# V1.net
KiCad netlist of a schematic drawn in EAGLE
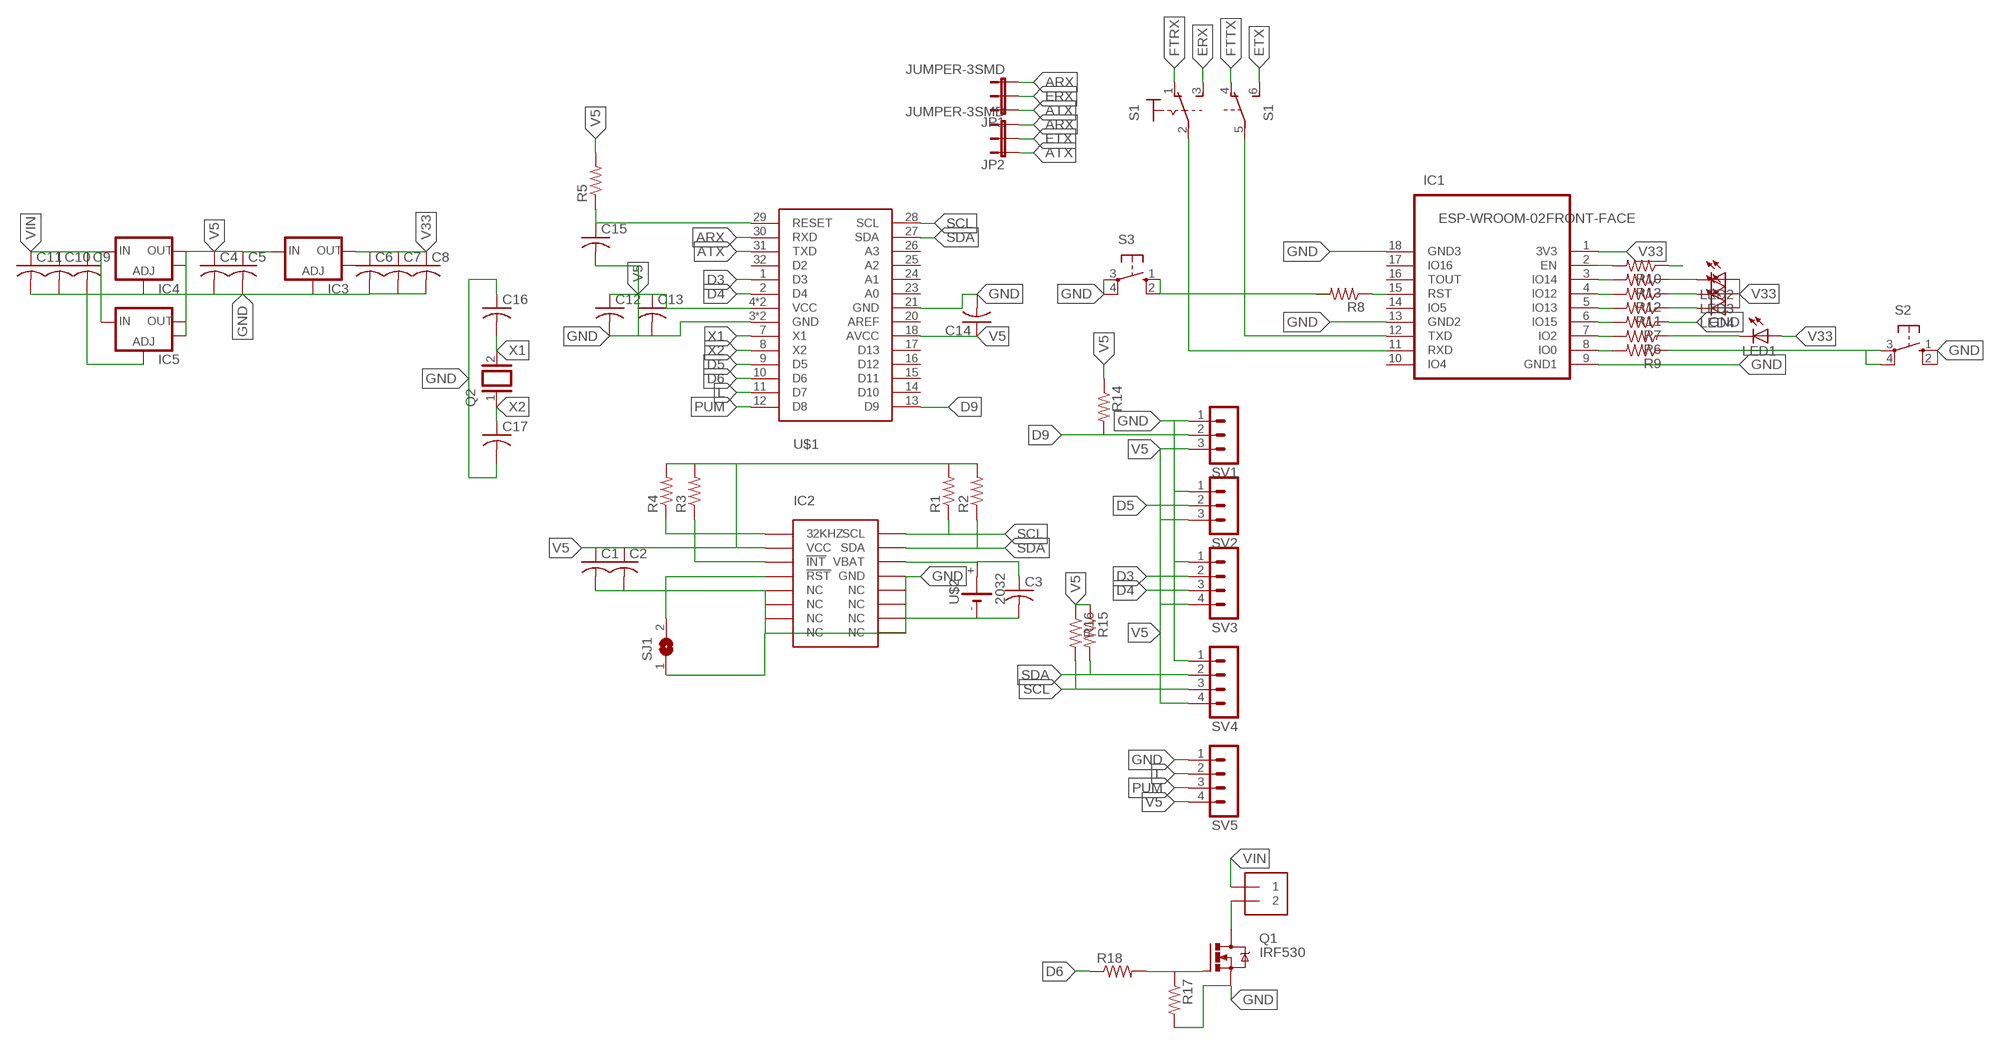
[diagram p0: schematic, sheet 1]

(export (version "E")
  (design (tool "Eeschema 10.0.6"))
  (components
    (comp (ref "C1")
      (value "C-USC0805")
      (footprint "eagle-import:C0805")
      (libsource (lib "eagle-import") (part "C-USC0805"))
    )
    (comp (ref "C2")
      (value "C-USC0805")
      (footprint "eagle-import:C0805")
      (libsource (lib "eagle-import") (part "C-USC0805"))
    )
    (comp (ref "C3")
      (value "C-USC0805")
      (footprint "eagle-import:C0805")
      (libsource (lib "eagle-import") (part "C-USC0805"))
    )
    (comp (ref "C4")
      (value "C-USC0805")
      (footprint "eagle-import:C0805")
      (libsource (lib "eagle-import") (part "C-USC0805"))
    )
    (comp (ref "C5")
      (value "C-USC0805")
      (footprint "eagle-import:C0805")
      (libsource (lib "eagle-import") (part "C-USC0805"))
    )
    (comp (ref "C6")
      (value "C-USC0805")
      (footprint "eagle-import:C0805")
      (libsource (lib "eagle-import") (part "C-USC0805"))
    )
    (comp (ref "C7")
      (value "C-USC0805")
      (footprint "eagle-import:C0805")
      (libsource (lib "eagle-import") (part "C-USC0805"))
    )
    (comp (ref "C8")
      (value "C-USC0805")
      (footprint "eagle-import:C0805")
      (libsource (lib "eagle-import") (part "C-USC0805"))
    )
    (comp (ref "C9")
      (value "C-USC0805")
      (footprint "eagle-import:C0805")
      (libsource (lib "eagle-import") (part "C-USC0805"))
    )
    (comp (ref "C10")
      (value "C-USC0805")
      (footprint "eagle-import:C0805")
      (libsource (lib "eagle-import") (part "C-USC0805"))
    )
    (comp (ref "C11")
      (value "C-USC0805")
      (footprint "eagle-import:C0805")
      (libsource (lib "eagle-import") (part "C-USC0805"))
    )
    (comp (ref "C12")
      (value "C-USC0805")
      (footprint "eagle-import:C0805")
      (libsource (lib "eagle-import") (part "C-USC0805"))
    )
    (comp (ref "C13")
      (value "C-USC0805")
      (footprint "eagle-import:C0805")
      (libsource (lib "eagle-import") (part "C-USC0805"))
    )
    (comp (ref "C14")
      (value "C-USC0805")
      (footprint "eagle-import:C0805")
      (libsource (lib "eagle-import") (part "C-USC0805"))
    )
    (comp (ref "C15")
      (value "C-USC0805")
      (footprint "eagle-import:C0805")
      (libsource (lib "eagle-import") (part "C-USC0805"))
    )
    (comp (ref "C16")
      (value "C-USC0805")
      (footprint "eagle-import:C0805")
      (libsource (lib "eagle-import") (part "C-USC0805"))
    )
    (comp (ref "C17")
      (value "C-USC0805")
      (footprint "eagle-import:C0805")
      (libsource (lib "eagle-import") (part "C-USC0805"))
    )
    (comp (ref "IC1")
      (value "ESP-WROOM-02FRONT-FACE")
      (footprint "eagle-import:FRONT-FACE")
      (libsource (lib "eagle-import") (part "ESP-WROOM-02FRONT-FACE"))
    )
    (comp (ref "IC2")
      (value "DS3231SOIC-16W")
      (footprint "eagle-import:SOIC-16W")
      (libsource (lib "eagle-import") (part "DS3231SOIC-16W"))
    )
    (comp (ref "IC3")
      (value "V_REG_LM1117SOT223")
      (footprint "eagle-import:SOT223")
      (libsource (lib "eagle-import") (part "V_REG_LM1117SOT223"))
    )
    (comp (ref "IC4")
      (value "V_REG_LM1117SOT223")
      (footprint "eagle-import:SOT223")
      (libsource (lib "eagle-import") (part "V_REG_LM1117SOT223"))
    )
    (comp (ref "IC5")
      (value "V_REG_LM1117SOT223")
      (footprint "eagle-import:SOT223")
      (libsource (lib "eagle-import") (part "V_REG_LM1117SOT223"))
    )
    (comp (ref "J1")
      (value "1X2-3.5MM")
      (footprint "eagle-import:3.5MMTERM")
      (libsource (lib "eagle-import") (part "1X2-3.5MM"))
    )
    (comp (ref "JP1")
      (value "JUMPER-3SMD")
      (footprint "eagle-import:SJ_3")
      (libsource (lib "eagle-import") (part "JUMPER-3SMD"))
    )
    (comp (ref "JP2")
      (value "JUMPER-3SMD")
      (footprint "eagle-import:SJ_3")
      (libsource (lib "eagle-import") (part "JUMPER-3SMD"))
    )
    (comp (ref "LED1")
      (value "LED5MM")
      (footprint "eagle-import:LED5MM")
      (libsource (lib "eagle-import") (part "LED5MM"))
    )
    (comp (ref "LED2")
      (value "LED5MM")
      (footprint "eagle-import:LED5MM")
      (libsource (lib "eagle-import") (part "LED5MM"))
    )
    (comp (ref "LED3")
      (value "LED5MM")
      (footprint "eagle-import:LED5MM")
      (libsource (lib "eagle-import") (part "LED5MM"))
    )
    (comp (ref "LED4")
      (value "LED5MM")
      (footprint "eagle-import:LED5MM")
      (libsource (lib "eagle-import") (part "LED5MM"))
    )
    (comp (ref "Q1")
      (value "IRF530")
      (footprint "eagle-import:TO220BV")
      (libsource (lib "eagle-import") (part "IRF530"))
    )
    (comp (ref "Q2")
      (value "XTAL/S")
      (footprint "eagle-import:QS")
      (libsource (lib "eagle-import") (part "XTAL/S"))
    )
    (comp (ref "R1")
      (value "R-US_R0805")
      (footprint "eagle-import:R0805")
      (libsource (lib "eagle-import") (part "R-US_R0805"))
    )
    (comp (ref "R2")
      (value "R-US_R0805")
      (footprint "eagle-import:R0805")
      (libsource (lib "eagle-import") (part "R-US_R0805"))
    )
    (comp (ref "R3")
      (value "R-US_R0805")
      (footprint "eagle-import:R0805")
      (libsource (lib "eagle-import") (part "R-US_R0805"))
    )
    (comp (ref "R4")
      (value "R-US_R0805")
      (footprint "eagle-import:R0805")
      (libsource (lib "eagle-import") (part "R-US_R0805"))
    )
    (comp (ref "R5")
      (value "R-US_R0805")
      (footprint "eagle-import:R0805")
      (libsource (lib "eagle-import") (part "R-US_R0805"))
    )
    (comp (ref "R6")
      (value "R-US_R0805")
      (footprint "eagle-import:R0805")
      (libsource (lib "eagle-import") (part "R-US_R0805"))
    )
    (comp (ref "R7")
      (value "R-US_R0805")
      (footprint "eagle-import:R0805")
      (libsource (lib "eagle-import") (part "R-US_R0805"))
    )
    (comp (ref "R8")
      (value "R-US_R0805")
      (footprint "eagle-import:R0805")
      (libsource (lib "eagle-import") (part "R-US_R0805"))
    )
    (comp (ref "R9")
      (value "R-US_R0805")
      (footprint "eagle-import:R0805")
      (libsource (lib "eagle-import") (part "R-US_R0805"))
    )
    (comp (ref "R10")
      (value "R-US_R0805")
      (footprint "eagle-import:R0805")
      (libsource (lib "eagle-import") (part "R-US_R0805"))
    )
    (comp (ref "R11")
      (value "R-US_R0805")
      (footprint "eagle-import:R0805")
      (libsource (lib "eagle-import") (part "R-US_R0805"))
    )
    (comp (ref "R12")
      (value "R-US_R0805")
      (footprint "eagle-import:R0805")
      (libsource (lib "eagle-import") (part "R-US_R0805"))
    )
    (comp (ref "R13")
      (value "R-US_R0805")
      (footprint "eagle-import:R0805")
      (libsource (lib "eagle-import") (part "R-US_R0805"))
    )
    (comp (ref "R14")
      (value "R-US_R0805")
      (footprint "eagle-import:R0805")
      (libsource (lib "eagle-import") (part "R-US_R0805"))
    )
    (comp (ref "R15")
      (value "R-US_R0805")
      (footprint "eagle-import:R0805")
      (libsource (lib "eagle-import") (part "R-US_R0805"))
    )
    (comp (ref "R16")
      (value "R-US_R0805")
      (footprint "eagle-import:R0805")
      (libsource (lib "eagle-import") (part "R-US_R0805"))
    )
    (comp (ref "R17")
      (value "R-US_R0805")
      (footprint "eagle-import:R0805")
      (libsource (lib "eagle-import") (part "R-US_R0805"))
    )
    (comp (ref "R18")
      (value "R-US_R0805")
      (footprint "eagle-import:R0805")
      (libsource (lib "eagle-import") (part "R-US_R0805"))
    )
    (comp (ref "S1")
      (value "320-938")
      (footprint "eagle-import:320-938")
      (libsource (lib "eagle-import") (part "320-938"))
    )
    (comp (ref "S2")
      (value "10-XX")
      (footprint "eagle-import:B3F-10XX")
      (fields (field (name "MPN") "B3F-1000"))
      (libsource (lib "eagle-import") (part "10-XX"))
    )
    (comp (ref "S3")
      (value "10-XX")
      (footprint "eagle-import:B3F-10XX")
      (fields (field (name "MPN") "B3F-1000"))
      (libsource (lib "eagle-import") (part "10-XX"))
    )
    (comp (ref "SJ1")
      (value "SJW")
      (footprint "eagle-import:SJW")
      (libsource (lib "eagle-import") (part "SJW"))
    )
    (comp (ref "SV1")
      (value "MA03-1")
      (footprint "eagle-import:MA03-1")
      (libsource (lib "eagle-import") (part "MA03-1"))
    )
    (comp (ref "SV2")
      (value "MA03-1")
      (footprint "eagle-import:MA03-1")
      (libsource (lib "eagle-import") (part "MA03-1"))
    )
    (comp (ref "SV3")
      (value "MA04-1")
      (footprint "eagle-import:MA04-1")
      (libsource (lib "eagle-import") (part "MA04-1"))
    )
    (comp (ref "SV4")
      (value "MA04-1")
      (footprint "eagle-import:MA04-1")
      (libsource (lib "eagle-import") (part "MA04-1"))
    )
    (comp (ref "SV5")
      (value "MA04-1")
      (footprint "eagle-import:MA04-1")
      (libsource (lib "eagle-import") (part "MA04-1"))
    )
    (comp (ref "U$1")
      (value "ATMEGA328P")
      (footprint "eagle-import:TQFP32-08")
      (libsource (lib "eagle-import") (part "ATMEGA328P"))
    )
    (comp (ref "U$2")
      (value "2032")
      (footprint "eagle-import:KZH20SMD")
      (libsource (lib "eagle-import") (part "2032"))
    )
  )
  (nets
    (net (code "1") (name "ARX") (class "Default")
      (node (ref "C15") (pin "1") (pinfunction "1_1") (pintype "passive"))
      (node (ref "JP1") (pin "3") (pinfunction "3_3") (pintype "passive"))
      (node (ref "JP2") (pin "3") (pinfunction "3_3") (pintype "passive"))
      (node (ref "R5") (pin "1") (pinfunction "1_1") (pintype "passive"))
      (node (ref "U$1") (pin "29") (pinfunction "RESET_29") (pintype "bidirectional"))
      (node (ref "U$1") (pin "30") (pinfunction "RXD_30") (pintype "bidirectional"))
    )
    (net (code "2") (name "ATX") (class "Default")
      (node (ref "JP1") (pin "1") (pinfunction "1_1") (pintype "passive"))
      (node (ref "JP2") (pin "1") (pinfunction "1_1") (pintype "passive"))
      (node (ref "U$1") (pin "31") (pinfunction "TXD_31") (pintype "bidirectional"))
    )
    (net (code "3") (name "D3") (class "Default")
      (node (ref "SV3") (pin "2") (pinfunction "2_2") (pintype "passive"))
      (node (ref "U$1") (pin "1") (pinfunction "D3_1") (pintype "bidirectional"))
    )
    (net (code "4") (name "D4") (class "Default")
      (node (ref "SV3") (pin "3") (pinfunction "3_3") (pintype "passive"))
      (node (ref "U$1") (pin "2") (pinfunction "D4_2") (pintype "bidirectional"))
    )
    (net (code "5") (name "D5") (class "Default")
      (node (ref "SV2") (pin "2") (pinfunction "2_2") (pintype "passive"))
      (node (ref "U$1") (pin "9") (pinfunction "D5_9") (pintype "bidirectional"))
    )
    (net (code "6") (name "D6") (class "Default")
      (node (ref "R18") (pin "1") (pinfunction "1_1") (pintype "passive"))
      (node (ref "U$1") (pin "10") (pinfunction "D6_10") (pintype "bidirectional"))
    )
    (net (code "7") (name "D9") (class "Default")
      (node (ref "R14") (pin "2") (pinfunction "2_2") (pintype "passive"))
      (node (ref "SV1") (pin "2") (pinfunction "2_2") (pintype "passive"))
      (node (ref "U$1") (pin "13") (pinfunction "D9_13") (pintype "bidirectional"))
    )
    (net (code "8") (name "ERX") (class "Default")
      (node (ref "JP1") (pin "2") (pinfunction "2_2") (pintype "passive"))
      (node (ref "S1") (pin "3") (pinfunction "S_3") (pintype "passive"))
    )
    (net (code "9") (name "ETX") (class "Default")
      (node (ref "JP2") (pin "2") (pinfunction "2_2") (pintype "passive"))
      (node (ref "S1") (pin "6") (pinfunction "S_6") (pintype "passive"))
    )
    (net (code "10") (name "FTRX") (class "Default")
      (node (ref "S1") (pin "1") (pinfunction "O_1") (pintype "passive"))
    )
    (net (code "11") (name "FTTX") (class "Default")
      (node (ref "S1") (pin "4") (pinfunction "O_4") (pintype "passive"))
    )
    (net (code "12") (name "GND") (class "Default")
      (node (ref "C1") (pin "2") (pinfunction "2_2") (pintype "passive"))
      (node (ref "C10") (pin "2") (pinfunction "2_2") (pintype "passive"))
      (node (ref "C11") (pin "2") (pinfunction "2_2") (pintype "passive"))
      (node (ref "C12") (pin "2") (pinfunction "2_2") (pintype "passive"))
      (node (ref "C13") (pin "2") (pinfunction "2_2") (pintype "passive"))
      (node (ref "C14") (pin "2") (pinfunction "2_2") (pintype "passive"))
      (node (ref "C15") (pin "2") (pinfunction "2_2") (pintype "passive"))
      (node (ref "C16") (pin "1") (pinfunction "1_1") (pintype "passive"))
      (node (ref "C17") (pin "2") (pinfunction "2_2") (pintype "passive"))
      (node (ref "C2") (pin "2") (pinfunction "2_2") (pintype "passive"))
      (node (ref "C3") (pin "2") (pinfunction "2_2") (pintype "passive"))
      (node (ref "C4") (pin "2") (pinfunction "2_2") (pintype "passive"))
      (node (ref "C5") (pin "2") (pinfunction "2_2") (pintype "passive"))
      (node (ref "C6") (pin "2") (pinfunction "2_2") (pintype "passive"))
      (node (ref "C7") (pin "2") (pinfunction "2_2") (pintype "passive"))
      (node (ref "C8") (pin "2") (pinfunction "2_2") (pintype "passive"))
      (node (ref "C9") (pin "2") (pinfunction "2_2") (pintype "passive"))
      (node (ref "IC1") (pin "13") (pinfunction "GND2_13") (pintype "power_in"))
      (node (ref "IC1") (pin "18") (pinfunction "GND3_18") (pintype "power_in"))
      (node (ref "IC1") (pin "9") (pinfunction "GND1_9") (pintype "power_in"))
      (node (ref "IC2") (pin "10") (pinfunction "NC_10") (pintype "bidirectional"))
      (node (ref "IC2") (pin "11") (pinfunction "NC_11") (pintype "bidirectional"))
      (node (ref "IC2") (pin "12") (pinfunction "NC_12") (pintype "bidirectional"))
      (node (ref "IC2") (pin "13") (pinfunction "GND_13") (pintype "bidirectional"))
      (node (ref "IC2") (pin "5") (pinfunction "NC_5") (pintype "bidirectional"))
      (node (ref "IC2") (pin "6") (pinfunction "NC_6") (pintype "bidirectional"))
      (node (ref "IC2") (pin "7") (pinfunction "NC_7") (pintype "bidirectional"))
      (node (ref "IC2") (pin "8") (pinfunction "NC_8") (pintype "bidirectional"))
      (node (ref "IC2") (pin "9") (pinfunction "NC_9") (pintype "bidirectional"))
      (node (ref "IC3") (pin "1") (pinfunction "ADJ_1") (pintype "input"))
      (node (ref "IC4") (pin "1") (pinfunction "ADJ_1") (pintype "input"))
      (node (ref "IC5") (pin "1") (pinfunction "ADJ_1") (pintype "input"))
      (node (ref "Q1") (pin "S") (pinfunction "S_S") (pintype "passive"))
      (node (ref "R17") (pin "2") (pinfunction "2_2") (pintype "passive"))
      (node (ref "R7") (pin "1") (pinfunction "1_1") (pintype "passive"))
      (node (ref "S2") (pin "1") (pinfunction "S_1") (pintype "passive"))
      (node (ref "S2") (pin "2") (pinfunction "S1_2") (pintype "passive"))
      (node (ref "S3") (pin "3") (pinfunction "P_3") (pintype "passive"))
      (node (ref "S3") (pin "4") (pinfunction "P1_4") (pintype "passive"))
      (node (ref "SJ1") (pin "1") (pinfunction "1_1") (pintype "passive"))
      (node (ref "SV1") (pin "1") (pinfunction "1_1") (pintype "passive"))
      (node (ref "SV2") (pin "1") (pinfunction "1_1") (pintype "passive"))
      (node (ref "SV3") (pin "1") (pinfunction "1_1") (pintype "passive"))
      (node (ref "SV4") (pin "1") (pinfunction "1_1") (pintype "passive"))
      (node (ref "SV5") (pin "1") (pinfunction "1_1") (pintype "passive"))
      (node (ref "U$1") (pin "21") (pinfunction "GND_21") (pintype "bidirectional"))
      (node (ref "U$1") (pin "3") (pinfunction "GND_3") (pintype "bidirectional"))
      (node (ref "U$1") (pin "5") (pinfunction "GND_5") (pintype "bidirectional"))
      (node (ref "U$2") (pin "-") (pinfunction "-_-") (pintype "passive"))
    )
    (net (code "13") (name "L") (class "Default")
      (node (ref "SV5") (pin "2") (pinfunction "2_2") (pintype "passive"))
      (node (ref "U$1") (pin "11") (pinfunction "D7_11") (pintype "bidirectional"))
    )
    (net (code "14") (name "Net-(IC1-EN)") (class "Default")
      (node (ref "IC1") (pin "2") (pinfunction "EN_2") (pintype "bidirectional"))
      (node (ref "R10") (pin "2") (pinfunction "2_2") (pintype "passive"))
    )
    (net (code "15") (name "Net-(IC1-IO0)") (class "Default")
      (node (ref "IC1") (pin "8") (pinfunction "IO0_8") (pintype "bidirectional"))
      (node (ref "R9") (pin "2") (pinfunction "2_2") (pintype "passive"))
    )
    (net (code "16") (name "Net-(IC1-IO2)") (class "Default")
      (node (ref "IC1") (pin "7") (pinfunction "IO2_7") (pintype "bidirectional"))
      (node (ref "R6") (pin "2") (pinfunction "2_2") (pintype "passive"))
    )
    (net (code "17") (name "Net-(IC1-IO12)") (class "Default")
      (node (ref "IC1") (pin "4") (pinfunction "IO12_4") (pintype "bidirectional"))
      (node (ref "R12") (pin "2") (pinfunction "2_2") (pintype "passive"))
    )
    (net (code "18") (name "Net-(IC1-IO13)") (class "Default")
      (node (ref "IC1") (pin "5") (pinfunction "IO13_5") (pintype "bidirectional"))
      (node (ref "R11") (pin "2") (pinfunction "2_2") (pintype "passive"))
    )
    (net (code "19") (name "Net-(IC1-IO14)") (class "Default")
      (node (ref "IC1") (pin "3") (pinfunction "IO14_3") (pintype "bidirectional"))
      (node (ref "R13") (pin "2") (pinfunction "2_2") (pintype "passive"))
    )
    (net (code "20") (name "Net-(IC1-IO15)") (class "Default")
      (node (ref "IC1") (pin "6") (pinfunction "IO15_6") (pintype "bidirectional"))
      (node (ref "R7") (pin "2") (pinfunction "2_2") (pintype "passive"))
    )
    (net (code "21") (name "Net-(IC1-RST)") (class "Default")
      (node (ref "IC1") (pin "15") (pinfunction "RST_15") (pintype "bidirectional"))
      (node (ref "R8") (pin "1") (pinfunction "1_1") (pintype "passive"))
    )
    (net (code "22") (name "Net-(IC1-RXD)") (class "Default")
      (node (ref "IC1") (pin "11") (pinfunction "RXD_11") (pintype "bidirectional"))
      (node (ref "S1") (pin "2") (pinfunction "P_2") (pintype "passive"))
    )
    (net (code "23") (name "Net-(IC1-TXD)") (class "Default")
      (node (ref "IC1") (pin "12") (pinfunction "TXD_12") (pintype "bidirectional"))
      (node (ref "S1") (pin "5") (pinfunction "P_5") (pintype "passive"))
    )
    (net (code "24") (name "Net-(IC2-32KHZ)") (class "Default")
      (node (ref "IC2") (pin "1") (pinfunction "32KHZ_1") (pintype "bidirectional"))
      (node (ref "R4") (pin "1") (pinfunction "1_1") (pintype "passive"))
    )
    (net (code "25") (name "Net-(IC2-VBAT)") (class "Default")
      (node (ref "C3") (pin "1") (pinfunction "1_1") (pintype "passive"))
      (node (ref "IC2") (pin "14") (pinfunction "VBAT_14") (pintype "bidirectional"))
      (node (ref "U$2") (pin "+") (pinfunction "+_+") (pintype "passive"))
    )
    (net (code "26") (name "Net-(IC2-~{INT})") (class "Default")
      (node (ref "IC2") (pin "3") (pinfunction "~{INT}_3") (pintype "bidirectional"))
      (node (ref "R3") (pin "1") (pinfunction "1_1") (pintype "passive"))
    )
    (net (code "27") (name "Net-(IC2-~{RST})") (class "Default")
      (node (ref "IC2") (pin "4") (pinfunction "~{RST}_4") (pintype "bidirectional"))
      (node (ref "SJ1") (pin "2") (pinfunction "2_2") (pintype "passive"))
    )
    (net (code "28") (name "Net-(J1-Pad2)") (class "Default")
      (node (ref "J1") (pin "2") (pinfunction "2_2") (pintype "passive"))
      (node (ref "Q1") (pin "D") (pinfunction "D_D") (pintype "passive"))
    )
    (net (code "29") (name "Net-(LED2-C)") (class "Default")
      (node (ref "LED2") (pin "K") (pinfunction "C_K") (pintype "passive"))
      (node (ref "R13") (pin "1") (pinfunction "1_1") (pintype "passive"))
    )
    (net (code "30") (name "Net-(LED3-C)") (class "Default")
      (node (ref "LED3") (pin "K") (pinfunction "C_K") (pintype "passive"))
      (node (ref "R12") (pin "1") (pinfunction "1_1") (pintype "passive"))
    )
    (net (code "31") (name "Net-(LED4-C)") (class "Default")
      (node (ref "LED4") (pin "K") (pinfunction "C_K") (pintype "passive"))
      (node (ref "R11") (pin "1") (pinfunction "1_1") (pintype "passive"))
    )
    (net (code "32") (name "Net-(Q1-PadG)") (class "Default")
      (node (ref "Q1") (pin "G") (pinfunction "G_G") (pintype "passive"))
      (node (ref "R17") (pin "1") (pinfunction "1_1") (pintype "passive"))
      (node (ref "R18") (pin "2") (pinfunction "2_2") (pintype "passive"))
    )
    (net (code "33") (name "Net-(S2-P)") (class "Default")
      (node (ref "R9") (pin "1") (pinfunction "1_1") (pintype "passive"))
      (node (ref "S2") (pin "3") (pinfunction "P_3") (pintype "passive"))
      (node (ref "S2") (pin "4") (pinfunction "P1_4") (pintype "passive"))
    )
    (net (code "34") (name "Net-(S3-S)") (class "Default")
      (node (ref "S3") (pin "1") (pinfunction "S_1") (pintype "passive"))
      (node (ref "S3") (pin "2") (pinfunction "S1_2") (pintype "passive"))
    )
    (net (code "35") (name "PUM") (class "Default")
      (node (ref "SV5") (pin "3") (pinfunction "3_3") (pintype "passive"))
      (node (ref "U$1") (pin "12") (pinfunction "D8_12") (pintype "bidirectional"))
    )
    (net (code "36") (name "SCL") (class "Default")
      (node (ref "IC2") (pin "16") (pinfunction "SCL_16") (pintype "bidirectional"))
      (node (ref "R1") (pin "1") (pinfunction "1_1") (pintype "passive"))
      (node (ref "R16") (pin "2") (pinfunction "2_2") (pintype "passive"))
      (node (ref "SV4") (pin "3") (pinfunction "3_3") (pintype "passive"))
      (node (ref "U$1") (pin "28") (pinfunction "SCL_28") (pintype "bidirectional"))
    )
    (net (code "37") (name "SDA") (class "Default")
      (node (ref "IC2") (pin "15") (pinfunction "SDA_15") (pintype "bidirectional"))
      (node (ref "R15") (pin "2") (pinfunction "2_2") (pintype "passive"))
      (node (ref "R2") (pin "1") (pinfunction "1_1") (pintype "passive"))
      (node (ref "SV4") (pin "2") (pinfunction "2_2") (pintype "passive"))
      (node (ref "U$1") (pin "27") (pinfunction "SDA_27") (pintype "bidirectional"))
    )
    (net (code "38") (name "V5") (class "Default")
      (node (ref "C1") (pin "1") (pinfunction "1_1") (pintype "passive"))
      (node (ref "C12") (pin "1") (pinfunction "1_1") (pintype "passive"))
      (node (ref "C13") (pin "1") (pinfunction "1_1") (pintype "passive"))
      (node (ref "C14") (pin "1") (pinfunction "1_1") (pintype "passive"))
      (node (ref "C2") (pin "1") (pinfunction "1_1") (pintype "passive"))
      (node (ref "C4") (pin "1") (pinfunction "1_1") (pintype "passive"))
      (node (ref "C5") (pin "1") (pinfunction "1_1") (pintype "passive"))
      (node (ref "IC2") (pin "2") (pinfunction "VCC_2") (pintype "bidirectional"))
      (node (ref "IC3") (pin "3") (pinfunction "IN_3") (pintype "input"))
      (node (ref "IC4") (pin "2") (pinfunction "OUT_2") (pintype "output"))
      (node (ref "IC4") (pin "4") (pinfunction "OUT_4") (pintype "output"))
      (node (ref "IC5") (pin "2") (pinfunction "OUT_2") (pintype "output"))
      (node (ref "IC5") (pin "4") (pinfunction "OUT_4") (pintype "output"))
      (node (ref "R1") (pin "2") (pinfunction "2_2") (pintype "passive"))
      (node (ref "R14") (pin "1") (pinfunction "1_1") (pintype "passive"))
      (node (ref "R15") (pin "1") (pinfunction "1_1") (pintype "passive"))
      (node (ref "R16") (pin "1") (pinfunction "1_1") (pintype "passive"))
      (node (ref "R2") (pin "2") (pinfunction "2_2") (pintype "passive"))
      (node (ref "R3") (pin "2") (pinfunction "2_2") (pintype "passive"))
      (node (ref "R4") (pin "2") (pinfunction "2_2") (pintype "passive"))
      (node (ref "R5") (pin "2") (pinfunction "2_2") (pintype "passive"))
      (node (ref "SV1") (pin "3") (pinfunction "3_3") (pintype "passive"))
      (node (ref "SV2") (pin "3") (pinfunction "3_3") (pintype "passive"))
      (node (ref "SV3") (pin "4") (pinfunction "4_4") (pintype "passive"))
      (node (ref "SV4") (pin "4") (pinfunction "4_4") (pintype "passive"))
      (node (ref "SV5") (pin "4") (pinfunction "4_4") (pintype "passive"))
      (node (ref "U$1") (pin "18") (pinfunction "AVCC_18") (pintype "bidirectional"))
      (node (ref "U$1") (pin "4") (pinfunction "VCC_4") (pintype "bidirectional"))
      (node (ref "U$1") (pin "6") (pinfunction "VCC_6") (pintype "bidirectional"))
    )
    (net (code "39") (name "V33") (class "Default")
      (node (ref "C6") (pin "1") (pinfunction "1_1") (pintype "passive"))
      (node (ref "C7") (pin "1") (pinfunction "1_1") (pintype "passive"))
      (node (ref "C8") (pin "1") (pinfunction "1_1") (pintype "passive"))
      (node (ref "IC1") (pin "1") (pinfunction "3V3_1") (pintype "power_in"))
      (node (ref "IC3") (pin "2") (pinfunction "OUT_2") (pintype "output"))
      (node (ref "LED1") (pin "A") (pinfunction "A_A") (pintype "passive"))
      (node (ref "LED1") (pin "K") (pinfunction "C_K") (pintype "passive"))
      (node (ref "LED2") (pin "A") (pinfunction "A_A") (pintype "passive"))
      (node (ref "LED3") (pin "A") (pinfunction "A_A") (pintype "passive"))
      (node (ref "LED4") (pin "A") (pinfunction "A_A") (pintype "passive"))
      (node (ref "R6") (pin "1") (pinfunction "1_1") (pintype "passive"))
    )
    (net (code "40") (name "VIN") (class "Default")
      (node (ref "C10") (pin "1") (pinfunction "1_1") (pintype "passive"))
      (node (ref "C11") (pin "1") (pinfunction "1_1") (pintype "passive"))
      (node (ref "C9") (pin "1") (pinfunction "1_1") (pintype "passive"))
      (node (ref "IC4") (pin "3") (pinfunction "IN_3") (pintype "input"))
      (node (ref "IC5") (pin "3") (pinfunction "IN_3") (pintype "input"))
      (node (ref "J1") (pin "1") (pinfunction "1_1") (pintype "passive"))
    )
    (net (code "41") (name "X1") (class "Default")
      (node (ref "C16") (pin "2") (pinfunction "2_2") (pintype "passive"))
      (node (ref "Q2") (pin "2") (pinfunction "2_2") (pintype "passive"))
      (node (ref "U$1") (pin "7") (pinfunction "X1_7") (pintype "bidirectional"))
    )
    (net (code "42") (name "X2") (class "Default")
      (node (ref "C17") (pin "1") (pinfunction "1_1") (pintype "passive"))
      (node (ref "Q2") (pin "1") (pinfunction "1_1") (pintype "passive"))
      (node (ref "U$1") (pin "8") (pinfunction "X2_8") (pintype "bidirectional"))
    )
    (net (code "43") (name "unconnected-(IC1-IO4-Pad10)") (class "Default")
      (node (ref "IC1") (pin "10") (pinfunction "IO4_10") (pintype "bidirectional"))
    )
    (net (code "44") (name "unconnected-(IC1-IO5-Pad14)") (class "Default")
      (node (ref "IC1") (pin "14") (pinfunction "IO5_14") (pintype "open_collector"))
    )
    (net (code "45") (name "unconnected-(IC1-IO16-Pad17)") (class "Default")
      (node (ref "IC1") (pin "17") (pinfunction "IO16_17") (pintype "bidirectional"))
    )
    (net (code "46") (name "unconnected-(IC1-TOUT-Pad16)") (class "Default")
      (node (ref "IC1") (pin "16") (pinfunction "TOUT_16") (pintype "bidirectional"))
    )
    (net (code "47") (name "unconnected-(IC3-OUT-Pad4)") (class "Default")
      (node (ref "IC3") (pin "4") (pinfunction "OUT_4") (pintype "output"))
    )
    (net (code "48") (name "unconnected-(R8-Pad2)") (class "Default")
      (node (ref "R8") (pin "2") (pinfunction "2_2") (pintype "passive"))
    )
    (net (code "49") (name "unconnected-(R10-Pad1)") (class "Default")
      (node (ref "R10") (pin "1") (pinfunction "1_1") (pintype "passive"))
    )
    (net (code "50") (name "unconnected-(U$1-A0-Pad23)") (class "Default")
      (node (ref "U$1") (pin "23") (pinfunction "A0_23") (pintype "bidirectional"))
    )
    (net (code "51") (name "unconnected-(U$1-A1-Pad24)") (class "Default")
      (node (ref "U$1") (pin "24") (pinfunction "A1_24") (pintype "bidirectional"))
    )
    (net (code "52") (name "unconnected-(U$1-A2-Pad25)") (class "Default")
      (node (ref "U$1") (pin "25") (pinfunction "A2_25") (pintype "bidirectional"))
    )
    (net (code "53") (name "unconnected-(U$1-A3-Pad26)") (class "Default")
      (node (ref "U$1") (pin "26") (pinfunction "A3_26") (pintype "bidirectional"))
    )
    (net (code "54") (name "unconnected-(U$1-AREF-Pad20)") (class "Default")
      (node (ref "U$1") (pin "20") (pinfunction "AREF_20") (pintype "bidirectional"))
    )
    (net (code "55") (name "unconnected-(U$1-D2-Pad32)") (class "Default")
      (node (ref "U$1") (pin "32") (pinfunction "D2_32") (pintype "bidirectional"))
    )
    (net (code "56") (name "unconnected-(U$1-D10-Pad14)") (class "Default")
      (node (ref "U$1") (pin "14") (pinfunction "D10_14") (pintype "bidirectional"))
    )
    (net (code "57") (name "unconnected-(U$1-D11-Pad15)") (class "Default")
      (node (ref "U$1") (pin "15") (pinfunction "D11_15") (pintype "bidirectional"))
    )
    (net (code "58") (name "unconnected-(U$1-D12-Pad16)") (class "Default")
      (node (ref "U$1") (pin "16") (pinfunction "D12_16") (pintype "bidirectional"))
    )
    (net (code "59") (name "unconnected-(U$1-D13-Pad17)") (class "Default")
      (node (ref "U$1") (pin "17") (pinfunction "D13_17") (pintype "bidirectional"))
    )
  )
)
